# Connections.net
KiCad netlist of a schematic drawn in Altium Designer
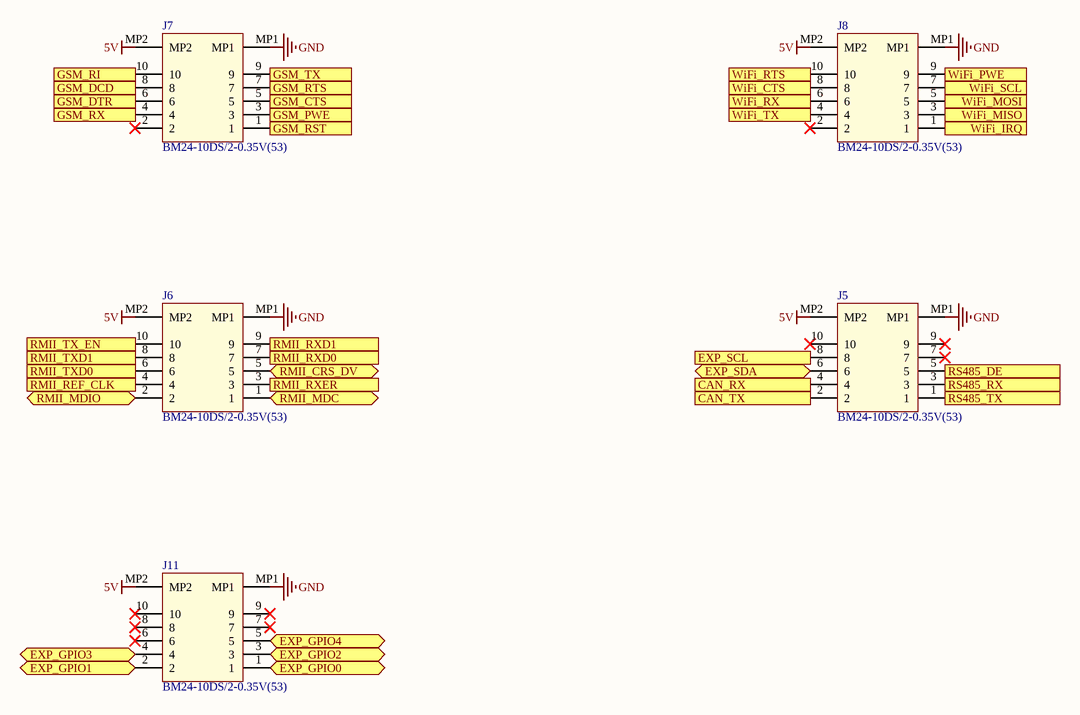
[diagram p0: Connections.SchDoc]

(export (version "E")
  (design (tool "Eeschema 10.0.6"))
  (components
    (comp (ref "J5")
      (value "BM24-10DS/2-0.35V(53)")
      (footprint "HIROSE BM2410DS")
      (description "Board to Board Connector")
      (fields (field (name "MANUFACTURER") "Hirose"))
      (libsource (lib "yildizIoT Library") (part "12 Pin (10 + 2 Power) B2B Socket"))
    )
    (comp (ref "J6")
      (value "BM24-10DS/2-0.35V(53)")
      (footprint "HIROSE BM2410DS")
      (description "Board to Board Connector")
      (fields (field (name "MANUFACTURER") "Hirose"))
      (libsource (lib "yildizIoT Library") (part "12 Pin (10 + 2 Power) B2B Socket"))
    )
    (comp (ref "J7")
      (value "BM24-10DS/2-0.35V(53)")
      (footprint "HIROSE BM2410DS")
      (description "Board to Board Connector")
      (fields (field (name "MANUFACTURER") "Hirose"))
      (libsource (lib "yildizIoT Library") (part "12 Pin (10 + 2 Power) B2B Socket"))
    )
    (comp (ref "J8")
      (value "BM24-10DS/2-0.35V(53)")
      (footprint "HIROSE BM2410DS")
      (description "Board to Board Connector")
      (fields (field (name "MANUFACTURER") "Hirose"))
      (libsource (lib "yildizIoT Library") (part "12 Pin (10 + 2 Power) B2B Socket"))
    )
    (comp (ref "J11")
      (value "BM24-10DS/2-0.35V(53)")
      (footprint "HIROSE BM2410DS")
      (description "Board to Board Connector")
      (fields (field (name "MANUFACTURER") "Hirose"))
      (libsource (lib "yildizIoT Library") (part "12 Pin (10 + 2 Power) B2B Socket"))
    )
  )
  (nets
    (net (code "1") (name "/CAN_RX") (class "Default")
      (node (ref "J5") (pin "4") (pinfunction "4_4") (pintype "passive"))
    )
    (net (code "2") (name "/CAN_TX") (class "Default")
      (node (ref "J5") (pin "2") (pinfunction "2_2") (pintype "passive"))
    )
    (net (code "3") (name "/EXP_GPIO0") (class "Default")
      (node (ref "J11") (pin "1") (pinfunction "1_1") (pintype "passive"))
    )
    (net (code "4") (name "/EXP_GPIO1") (class "Default")
      (node (ref "J11") (pin "2") (pinfunction "2_2") (pintype "passive"))
    )
    (net (code "5") (name "/EXP_GPIO2") (class "Default")
      (node (ref "J11") (pin "3") (pinfunction "3_3") (pintype "passive"))
    )
    (net (code "6") (name "/EXP_GPIO3") (class "Default")
      (node (ref "J11") (pin "4") (pinfunction "4_4") (pintype "passive"))
    )
    (net (code "7") (name "/EXP_GPIO4") (class "Default")
      (node (ref "J11") (pin "5") (pinfunction "5_5") (pintype "passive"))
    )
    (net (code "8") (name "/EXP_SCL") (class "Default")
      (node (ref "J5") (pin "8") (pinfunction "8_8") (pintype "passive"))
    )
    (net (code "9") (name "/EXP_SDA") (class "Default")
      (node (ref "J5") (pin "6") (pinfunction "6_6") (pintype "passive"))
    )
    (net (code "10") (name "/GSM_CTS") (class "Default")
      (node (ref "J7") (pin "5") (pinfunction "5_5") (pintype "passive"))
    )
    (net (code "11") (name "/GSM_DCD") (class "Default")
      (node (ref "J7") (pin "8") (pinfunction "8_8") (pintype "passive"))
    )
    (net (code "12") (name "/GSM_DTR") (class "Default")
      (node (ref "J7") (pin "6") (pinfunction "6_6") (pintype "passive"))
    )
    (net (code "13") (name "/GSM_PWE") (class "Default")
      (node (ref "J7") (pin "3") (pinfunction "3_3") (pintype "passive"))
    )
    (net (code "14") (name "/GSM_RI") (class "Default")
      (node (ref "J7") (pin "10") (pinfunction "10_10") (pintype "passive"))
    )
    (net (code "15") (name "/GSM_RST") (class "Default")
      (node (ref "J7") (pin "1") (pinfunction "1_1") (pintype "passive"))
    )
    (net (code "16") (name "/GSM_RTS") (class "Default")
      (node (ref "J7") (pin "7") (pinfunction "7_7") (pintype "passive"))
    )
    (net (code "17") (name "/GSM_RX") (class "Default")
      (node (ref "J7") (pin "4") (pinfunction "4_4") (pintype "passive"))
    )
    (net (code "18") (name "/GSM_TX") (class "Default")
      (node (ref "J7") (pin "9") (pinfunction "9_9") (pintype "passive"))
    )
    (net (code "19") (name "/RMII_CRS_DV") (class "Default")
      (node (ref "J6") (pin "5") (pinfunction "5_5") (pintype "passive"))
    )
    (net (code "20") (name "/RMII_MDC") (class "Default")
      (node (ref "J6") (pin "1") (pinfunction "1_1") (pintype "passive"))
    )
    (net (code "21") (name "/RMII_MDIO") (class "Default")
      (node (ref "J6") (pin "2") (pinfunction "2_2") (pintype "passive"))
    )
    (net (code "22") (name "/RMII_REF_CLK") (class "Default")
      (node (ref "J6") (pin "4") (pinfunction "4_4") (pintype "passive"))
    )
    (net (code "23") (name "/RMII_RXD0") (class "Default")
      (node (ref "J6") (pin "7") (pinfunction "7_7") (pintype "passive"))
    )
    (net (code "24") (name "/RMII_RXD1") (class "Default")
      (node (ref "J6") (pin "9") (pinfunction "9_9") (pintype "passive"))
    )
    (net (code "25") (name "/RMII_RXER") (class "Default")
      (node (ref "J6") (pin "3") (pinfunction "3_3") (pintype "passive"))
    )
    (net (code "26") (name "/RMII_TXD0") (class "Default")
      (node (ref "J6") (pin "6") (pinfunction "6_6") (pintype "passive"))
    )
    (net (code "27") (name "/RMII_TXD1") (class "Default")
      (node (ref "J6") (pin "8") (pinfunction "8_8") (pintype "passive"))
    )
    (net (code "28") (name "/RMII_TX_EN") (class "Default")
      (node (ref "J6") (pin "10") (pinfunction "10_10") (pintype "passive"))
    )
    (net (code "29") (name "/RS485_DE") (class "Default")
      (node (ref "J5") (pin "5") (pinfunction "5_5") (pintype "passive"))
    )
    (net (code "30") (name "/RS485_RX") (class "Default")
      (node (ref "J5") (pin "3") (pinfunction "3_3") (pintype "passive"))
    )
    (net (code "31") (name "/RS485_TX") (class "Default")
      (node (ref "J5") (pin "1") (pinfunction "1_1") (pintype "passive"))
    )
    (net (code "32") (name "/WiFi_CTS") (class "Default")
      (node (ref "J8") (pin "8") (pinfunction "8_8") (pintype "passive"))
    )
    (net (code "33") (name "/WiFi_IRQ") (class "Default")
      (node (ref "J8") (pin "1") (pinfunction "1_1") (pintype "passive"))
    )
    (net (code "34") (name "/WiFi_MISO") (class "Default")
      (node (ref "J8") (pin "3") (pinfunction "3_3") (pintype "passive"))
    )
    (net (code "35") (name "/WiFi_MOSI") (class "Default")
      (node (ref "J8") (pin "5") (pinfunction "5_5") (pintype "passive"))
    )
    (net (code "36") (name "/WiFi_PWE") (class "Default")
      (node (ref "J8") (pin "9") (pinfunction "9_9") (pintype "passive"))
    )
    (net (code "37") (name "/WiFi_RTS") (class "Default")
      (node (ref "J8") (pin "10") (pinfunction "10_10") (pintype "passive"))
    )
    (net (code "38") (name "/WiFi_RX") (class "Default")
      (node (ref "J8") (pin "6") (pinfunction "6_6") (pintype "passive"))
    )
    (net (code "39") (name "/WiFi_SCL") (class "Default")
      (node (ref "J8") (pin "7") (pinfunction "7_7") (pintype "passive"))
    )
    (net (code "40") (name "/WiFi_TX") (class "Default")
      (node (ref "J8") (pin "4") (pinfunction "4_4") (pintype "passive"))
    )
    (net (code "41") (name "5V") (class "Default")
      (node (ref "J11") (pin "MP2") (pinfunction "MP2_MP2") (pintype "passive"))
      (node (ref "J5") (pin "MP2") (pinfunction "MP2_MP2") (pintype "passive"))
      (node (ref "J6") (pin "MP2") (pinfunction "MP2_MP2") (pintype "passive"))
      (node (ref "J7") (pin "MP2") (pinfunction "MP2_MP2") (pintype "passive"))
      (node (ref "J8") (pin "MP2") (pinfunction "MP2_MP2") (pintype "passive"))
    )
    (net (code "42") (name "GND") (class "Default")
      (node (ref "J11") (pin "MP1") (pinfunction "MP1_MP1") (pintype "passive"))
      (node (ref "J5") (pin "MP1") (pinfunction "MP1_MP1") (pintype "passive"))
      (node (ref "J6") (pin "MP1") (pinfunction "MP1_MP1") (pintype "passive"))
      (node (ref "J7") (pin "MP1") (pinfunction "MP1_MP1") (pintype "passive"))
      (node (ref "J8") (pin "MP1") (pinfunction "MP1_MP1") (pintype "passive"))
    )
    (net (code "43") (name "unconnected-(J5-Pad7)") (class "Default")
      (node (ref "J5") (pin "7") (pinfunction "7_7") (pintype "passive+no_connect"))
    )
    (net (code "44") (name "unconnected-(J5-Pad9)") (class "Default")
      (node (ref "J5") (pin "9") (pinfunction "9_9") (pintype "passive+no_connect"))
    )
    (net (code "45") (name "unconnected-(J5-Pad10)") (class "Default")
      (node (ref "J5") (pin "10") (pinfunction "10_10") (pintype "passive+no_connect"))
    )
    (net (code "46") (name "unconnected-(J7-Pad2)") (class "Default")
      (node (ref "J7") (pin "2") (pinfunction "2_2") (pintype "passive+no_connect"))
    )
    (net (code "47") (name "unconnected-(J8-Pad2)") (class "Default")
      (node (ref "J8") (pin "2") (pinfunction "2_2") (pintype "passive+no_connect"))
    )
    (net (code "48") (name "unconnected-(J11-Pad6)") (class "Default")
      (node (ref "J11") (pin "6") (pinfunction "6_6") (pintype "passive+no_connect"))
    )
    (net (code "49") (name "unconnected-(J11-Pad7)") (class "Default")
      (node (ref "J11") (pin "7") (pinfunction "7_7") (pintype "passive+no_connect"))
    )
    (net (code "50") (name "unconnected-(J11-Pad8)") (class "Default")
      (node (ref "J11") (pin "8") (pinfunction "8_8") (pintype "passive+no_connect"))
    )
    (net (code "51") (name "unconnected-(J11-Pad9)") (class "Default")
      (node (ref "J11") (pin "9") (pinfunction "9_9") (pintype "passive+no_connect"))
    )
    (net (code "52") (name "unconnected-(J11-Pad10)") (class "Default")
      (node (ref "J11") (pin "10") (pinfunction "10_10") (pintype "passive+no_connect"))
    )
  )
)
